# LVDS_IFC_HVAMP.net
KiCad netlist of a schematic drawn in Altium Designer
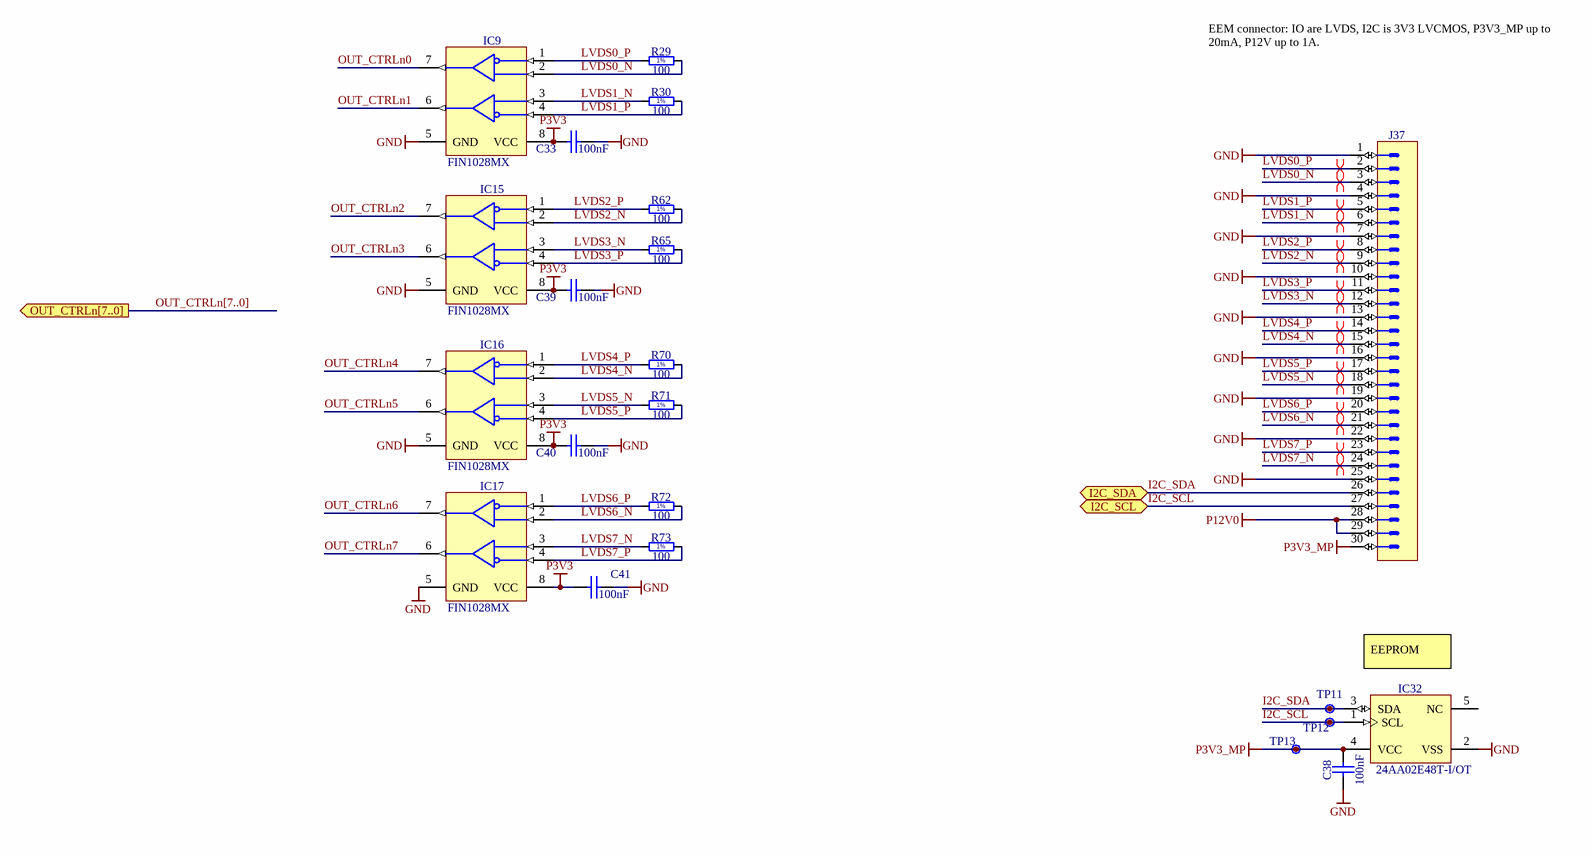
[diagram p0: LVDS_IFC_HVAMP.SchDoc]

(export (version "E")
  (design (tool "Eeschema 10.0.6"))
  (components
    (comp (ref "C33")
      (value "100nF")
      (footprint "CAPC1005X55N")
      (description "Non-polarised capacitor")
      (fields
        (field (name "PART NUMBER") "CC0402_100NF_16V_10%_X5R")
        (field (name "VOLTAGE") "16V")
        (field (name "AUTHOR") "CERN DEM JLC")
      )
      (libsource (lib "Capacitors") (part "Capacitor - non polarized"))
    )
    (comp (ref "C38")
      (value "100nF")
      (footprint "CAPC1005X55N")
      (description "Non-polarised capacitor")
      (fields
        (field (name "PART NUMBER") "CC0402_100NF_16V_10%_X5R")
        (field (name "VOLTAGE") "16V")
        (field (name "AUTHOR") "CERN DEM JLC")
      )
      (libsource (lib "Capacitors") (part "Capacitor - non polarized"))
    )
    (comp (ref "C39")
      (value "100nF")
      (footprint "CAPC1005X55N")
      (description "Non-polarised capacitor")
      (fields
        (field (name "PART NUMBER") "CC0402_100NF_16V_10%_X5R")
        (field (name "VOLTAGE") "16V")
        (field (name "AUTHOR") "CERN DEM JLC")
      )
      (libsource (lib "Capacitors") (part "Capacitor - non polarized"))
    )
    (comp (ref "C40")
      (value "100nF")
      (footprint "CAPC1005X55N")
      (description "Non-polarised capacitor")
      (fields
        (field (name "PART NUMBER") "CC0402_100NF_16V_10%_X5R")
        (field (name "VOLTAGE") "16V")
        (field (name "AUTHOR") "CERN DEM JLC")
      )
      (libsource (lib "Capacitors") (part "Capacitor - non polarized"))
    )
    (comp (ref "C41")
      (value "100nF")
      (footprint "CAPC1005X55N")
      (description "Non-polarised capacitor")
      (fields
        (field (name "PART NUMBER") "CC0402_100NF_16V_10%_X5R")
        (field (name "VOLTAGE") "16V")
        (field (name "AUTHOR") "CERN DEM JLC")
      )
      (libsource (lib "Capacitors") (part "Capacitor - non polarized"))
    )
    (comp (ref "IC9")
      (value "FIN1028MX")
      (footprint "SOIC127P600X175-8N")
      (description "3.3V LVDS 2-Bit High-Speed Differential Reciever")
      (fields (field (name "MANUFACTURER") "ON Semiconductor") (field (name "AUTHOR") "GK"))
      (libsource (lib "LIBRARY_SCH") (part "IFC_FIN1028"))
    )
    (comp (ref "IC15")
      (value "FIN1028MX")
      (footprint "SOIC127P600X175-8N")
      (description "3.3V LVDS 2-Bit High-Speed Differential Reciever")
      (fields (field (name "MANUFACTURER") "ON Semiconductor") (field (name "AUTHOR") "GK"))
      (libsource (lib "LIBRARY_SCH") (part "IFC_FIN1028"))
    )
    (comp (ref "IC16")
      (value "FIN1028MX")
      (footprint "SOIC127P600X175-8N")
      (description "3.3V LVDS 2-Bit High-Speed Differential Reciever")
      (fields (field (name "MANUFACTURER") "ON Semiconductor") (field (name "AUTHOR") "GK"))
      (libsource (lib "LIBRARY_SCH") (part "IFC_FIN1028"))
    )
    (comp (ref "IC17")
      (value "FIN1028MX")
      (footprint "SOIC127P600X175-8N")
      (description "3.3V LVDS 2-Bit High-Speed Differential Reciever")
      (fields (field (name "MANUFACTURER") "ON Semiconductor") (field (name "AUTHOR") "GK"))
      (libsource (lib "LIBRARY_SCH") (part "IFC_FIN1028"))
    )
    (comp (ref "IC32")
      (value "24AA02E48T-I/OT")
      (footprint "SOT95P280X145-5N")
      (description "1.7V-5.5V, 2K I2C Serial EEPROM With EUI-48 Node Identity")
      (fields (field (name "MANUFACTURER") "MICROCHIP TECHNOLOGY") (field (name "AUTHOR") "CERN DEM MR"))
      (libsource (lib "ICs And Semiconductors") (part "24AA02E48T-I/OT"))
    )
    (comp (ref "J37")
      (value "~")
      (footprint "3M_N2530-6002RB")
      (description "Connector 30 Male")
      (fields
        (field (name "PART NUMBER") "3M_N2530-6002RB")
        (field (name "MANUFACTURER") "3M")
        (field (name "AUTHOR") "CERN DEM JLC")
      )
      (libsource (lib "Connectors") (part "Connector 30 Male"))
    )
    (comp (ref "R29")
      (value "100")
      (footprint "RESC1005X40N")
      (description "Resistor - 1%")
      (fields
        (field (name "PART NUMBER") "R0402_100R_1%_0.0625W_100PPM")
        (field (name "POWER") "0.0625W")
        (field (name "AUTHOR") "CERN DEM JLC")
      )
      (libsource (lib "Resistors") (part "Resistor - 1%"))
    )
    (comp (ref "R30")
      (value "100")
      (footprint "RESC1005X40N")
      (description "Resistor - 1%")
      (fields
        (field (name "PART NUMBER") "R0402_100R_1%_0.0625W_100PPM")
        (field (name "POWER") "0.0625W")
        (field (name "AUTHOR") "CERN DEM JLC")
      )
      (libsource (lib "Resistors") (part "Resistor - 1%"))
    )
    (comp (ref "R62")
      (value "100")
      (footprint "RESC1005X40N")
      (description "Resistor - 1%")
      (fields
        (field (name "PART NUMBER") "R0402_100R_1%_0.0625W_100PPM")
        (field (name "POWER") "0.0625W")
        (field (name "AUTHOR") "CERN DEM JLC")
      )
      (libsource (lib "Resistors") (part "Resistor - 1%"))
    )
    (comp (ref "R65")
      (value "100")
      (footprint "RESC1005X40N")
      (description "Resistor - 1%")
      (fields
        (field (name "PART NUMBER") "R0402_100R_1%_0.0625W_100PPM")
        (field (name "POWER") "0.0625W")
        (field (name "AUTHOR") "CERN DEM JLC")
      )
      (libsource (lib "Resistors") (part "Resistor - 1%"))
    )
    (comp (ref "R70")
      (value "100")
      (footprint "RESC1005X40N")
      (description "Resistor - 1%")
      (fields
        (field (name "PART NUMBER") "R0402_100R_1%_0.0625W_100PPM")
        (field (name "POWER") "0.0625W")
        (field (name "AUTHOR") "CERN DEM JLC")
      )
      (libsource (lib "Resistors") (part "Resistor - 1%"))
    )
    (comp (ref "R71")
      (value "100")
      (footprint "RESC1005X40N")
      (description "Resistor - 1%")
      (fields
        (field (name "PART NUMBER") "R0402_100R_1%_0.0625W_100PPM")
        (field (name "POWER") "0.0625W")
        (field (name "AUTHOR") "CERN DEM JLC")
      )
      (libsource (lib "Resistors") (part "Resistor - 1%"))
    )
    (comp (ref "R72")
      (value "100")
      (footprint "RESC1005X40N")
      (description "Resistor - 1%")
      (fields
        (field (name "PART NUMBER") "R0402_100R_1%_0.0625W_100PPM")
        (field (name "POWER") "0.0625W")
        (field (name "AUTHOR") "CERN DEM JLC")
      )
      (libsource (lib "Resistors") (part "Resistor - 1%"))
    )
    (comp (ref "R73")
      (value "100")
      (footprint "RESC1005X40N")
      (description "Resistor - 1%")
      (fields
        (field (name "PART NUMBER") "R0402_100R_1%_0.0625W_100PPM")
        (field (name "POWER") "0.0625W")
        (field (name "AUTHOR") "CERN DEM JLC")
      )
      (libsource (lib "Resistors") (part "Resistor - 1%"))
    )
    (comp (ref "TP11")
      (value "Test Point")
      (footprint "TPS127")
      (fields (field (name "PART NUMBER") "SMD_PAD_1.27X1.27MM") (field (name "AUTHOR") "CERN DEM JLC"))
      (libsource (lib "Eletro-mechanical") (part "Test Point"))
    )
    (comp (ref "TP12")
      (value "Test Point")
      (footprint "TPS127")
      (fields (field (name "PART NUMBER") "SMD_PAD_1.27X1.27MM") (field (name "AUTHOR") "CERN DEM JLC"))
      (libsource (lib "Eletro-mechanical") (part "Test Point"))
    )
    (comp (ref "TP13")
      (value "Test Point")
      (footprint "TPS127")
      (fields (field (name "PART NUMBER") "SMD_PAD_1.27X1.27MM") (field (name "AUTHOR") "CERN DEM JLC"))
      (libsource (lib "Eletro-mechanical") (part "Test Point"))
    )
  )
  (nets
    (net (code "1") (name "/I2C_SCL") (class "Default")
      (node (ref "IC32") (pin "1") (pinfunction "SCL_1") (pintype "input"))
      (node (ref "J37") (pin "27") (pinfunction "27_27") (pintype "bidirectional"))
      (node (ref "TP12") (pin "1") (pinfunction "1_1") (pintype "bidirectional"))
    )
    (net (code "2") (name "/I2C_SDA") (class "Default")
      (node (ref "IC32") (pin "3") (pinfunction "SDA_3") (pintype "bidirectional"))
      (node (ref "J37") (pin "26") (pinfunction "26_26") (pintype "bidirectional"))
      (node (ref "TP11") (pin "1") (pinfunction "1_1") (pintype "bidirectional"))
    )
    (net (code "3") (name "/LVDS0_N") (class "Default")
      (node (ref "IC9") (pin "2") (pinfunction "RIN1+_2") (pintype "input"))
      (node (ref "J37") (pin "3") (pinfunction "3_3") (pintype "bidirectional"))
      (node (ref "R29") (pin "2") (pinfunction "2_2") (pintype "passive"))
    )
    (net (code "4") (name "/LVDS0_P") (class "Default")
      (node (ref "IC9") (pin "1") (pinfunction "RIN1-_1") (pintype "input"))
      (node (ref "J37") (pin "2") (pinfunction "2_2") (pintype "bidirectional"))
      (node (ref "R29") (pin "1") (pinfunction "1_1") (pintype "passive"))
    )
    (net (code "5") (name "/LVDS1_N") (class "Default")
      (node (ref "IC9") (pin "3") (pinfunction "RIN2+_3") (pintype "input"))
      (node (ref "J37") (pin "6") (pinfunction "6_6") (pintype "bidirectional"))
      (node (ref "R30") (pin "1") (pinfunction "1_1") (pintype "passive"))
    )
    (net (code "6") (name "/LVDS1_P") (class "Default")
      (node (ref "IC9") (pin "4") (pinfunction "RIN2-_4") (pintype "input"))
      (node (ref "J37") (pin "5") (pinfunction "5_5") (pintype "bidirectional"))
      (node (ref "R30") (pin "2") (pinfunction "2_2") (pintype "passive"))
    )
    (net (code "7") (name "/LVDS2_N") (class "Default")
      (node (ref "IC15") (pin "2") (pinfunction "RIN1+_2") (pintype "input"))
      (node (ref "J37") (pin "9") (pinfunction "9_9") (pintype "bidirectional"))
      (node (ref "R62") (pin "2") (pinfunction "2_2") (pintype "passive"))
    )
    (net (code "8") (name "/LVDS2_P") (class "Default")
      (node (ref "IC15") (pin "1") (pinfunction "RIN1-_1") (pintype "input"))
      (node (ref "J37") (pin "8") (pinfunction "8_8") (pintype "bidirectional"))
      (node (ref "R62") (pin "1") (pinfunction "1_1") (pintype "passive"))
    )
    (net (code "9") (name "/LVDS3_N") (class "Default")
      (node (ref "IC15") (pin "3") (pinfunction "RIN2+_3") (pintype "input"))
      (node (ref "J37") (pin "12") (pinfunction "12_12") (pintype "bidirectional"))
      (node (ref "R65") (pin "1") (pinfunction "1_1") (pintype "passive"))
    )
    (net (code "10") (name "/LVDS3_P") (class "Default")
      (node (ref "IC15") (pin "4") (pinfunction "RIN2-_4") (pintype "input"))
      (node (ref "J37") (pin "11") (pinfunction "11_11") (pintype "bidirectional"))
      (node (ref "R65") (pin "2") (pinfunction "2_2") (pintype "passive"))
    )
    (net (code "11") (name "/LVDS4_N") (class "Default")
      (node (ref "IC16") (pin "2") (pinfunction "RIN1+_2") (pintype "input"))
      (node (ref "J37") (pin "15") (pinfunction "15_15") (pintype "bidirectional"))
      (node (ref "R70") (pin "2") (pinfunction "2_2") (pintype "passive"))
    )
    (net (code "12") (name "/LVDS4_P") (class "Default")
      (node (ref "IC16") (pin "1") (pinfunction "RIN1-_1") (pintype "input"))
      (node (ref "J37") (pin "14") (pinfunction "14_14") (pintype "bidirectional"))
      (node (ref "R70") (pin "1") (pinfunction "1_1") (pintype "passive"))
    )
    (net (code "13") (name "/LVDS5_N") (class "Default")
      (node (ref "IC16") (pin "3") (pinfunction "RIN2+_3") (pintype "input"))
      (node (ref "J37") (pin "18") (pinfunction "18_18") (pintype "bidirectional"))
      (node (ref "R71") (pin "1") (pinfunction "1_1") (pintype "passive"))
    )
    (net (code "14") (name "/LVDS5_P") (class "Default")
      (node (ref "IC16") (pin "4") (pinfunction "RIN2-_4") (pintype "input"))
      (node (ref "J37") (pin "17") (pinfunction "17_17") (pintype "bidirectional"))
      (node (ref "R71") (pin "2") (pinfunction "2_2") (pintype "passive"))
    )
    (net (code "15") (name "/LVDS6_N") (class "Default")
      (node (ref "IC17") (pin "2") (pinfunction "RIN1+_2") (pintype "input"))
      (node (ref "J37") (pin "21") (pinfunction "21_21") (pintype "bidirectional"))
      (node (ref "R72") (pin "2") (pinfunction "2_2") (pintype "passive"))
    )
    (net (code "16") (name "/LVDS6_P") (class "Default")
      (node (ref "IC17") (pin "1") (pinfunction "RIN1-_1") (pintype "input"))
      (node (ref "J37") (pin "20") (pinfunction "20_20") (pintype "bidirectional"))
      (node (ref "R72") (pin "1") (pinfunction "1_1") (pintype "passive"))
    )
    (net (code "17") (name "/LVDS7_N") (class "Default")
      (node (ref "IC17") (pin "3") (pinfunction "RIN2+_3") (pintype "input"))
      (node (ref "J37") (pin "24") (pinfunction "24_24") (pintype "bidirectional"))
      (node (ref "R73") (pin "1") (pinfunction "1_1") (pintype "passive"))
    )
    (net (code "18") (name "/LVDS7_P") (class "Default")
      (node (ref "IC17") (pin "4") (pinfunction "RIN2-_4") (pintype "input"))
      (node (ref "J37") (pin "23") (pinfunction "23_23") (pintype "bidirectional"))
      (node (ref "R73") (pin "2") (pinfunction "2_2") (pintype "passive"))
    )
    (net (code "19") (name "/OUT_CTRLn0") (class "Default")
      (node (ref "IC9") (pin "7") (pinfunction "ROUT1_7") (pintype "output"))
    )
    (net (code "20") (name "/OUT_CTRLn1") (class "Default")
      (node (ref "IC9") (pin "6") (pinfunction "ROUT2_6") (pintype "output"))
    )
    (net (code "21") (name "/OUT_CTRLn2") (class "Default")
      (node (ref "IC15") (pin "7") (pinfunction "ROUT1_7") (pintype "output"))
    )
    (net (code "22") (name "/OUT_CTRLn3") (class "Default")
      (node (ref "IC15") (pin "6") (pinfunction "ROUT2_6") (pintype "output"))
    )
    (net (code "23") (name "/OUT_CTRLn4") (class "Default")
      (node (ref "IC16") (pin "7") (pinfunction "ROUT1_7") (pintype "output"))
    )
    (net (code "24") (name "/OUT_CTRLn5") (class "Default")
      (node (ref "IC16") (pin "6") (pinfunction "ROUT2_6") (pintype "output"))
    )
    (net (code "25") (name "/OUT_CTRLn6") (class "Default")
      (node (ref "IC17") (pin "7") (pinfunction "ROUT1_7") (pintype "output"))
    )
    (net (code "26") (name "/OUT_CTRLn7") (class "Default")
      (node (ref "IC17") (pin "6") (pinfunction "ROUT2_6") (pintype "output"))
    )
    (net (code "28") (name "GND") (class "Default")
      (node (ref "C33") (pin "1") (pinfunction "1_1") (pintype "passive"))
      (node (ref "C38") (pin "1") (pinfunction "1_1") (pintype "passive"))
      (node (ref "C39") (pin "1") (pinfunction "1_1") (pintype "passive"))
      (node (ref "C40") (pin "1") (pinfunction "1_1") (pintype "passive"))
      (node (ref "C41") (pin "1") (pinfunction "1_1") (pintype "passive"))
      (node (ref "IC15") (pin "5") (pinfunction "GND_5") (pintype "power_in"))
      (node (ref "IC16") (pin "5") (pinfunction "GND_5") (pintype "power_in"))
      (node (ref "IC17") (pin "5") (pinfunction "GND_5") (pintype "power_in"))
      (node (ref "IC32") (pin "2") (pinfunction "VSS_2") (pintype "power_in"))
      (node (ref "IC9") (pin "5") (pinfunction "GND_5") (pintype "power_in"))
      (node (ref "J37") (pin "1") (pinfunction "1_1") (pintype "bidirectional"))
      (node (ref "J37") (pin "10") (pinfunction "10_10") (pintype "bidirectional"))
      (node (ref "J37") (pin "13") (pinfunction "13_13") (pintype "bidirectional"))
      (node (ref "J37") (pin "16") (pinfunction "16_16") (pintype "bidirectional"))
      (node (ref "J37") (pin "19") (pinfunction "19_19") (pintype "bidirectional"))
      (node (ref "J37") (pin "22") (pinfunction "22_22") (pintype "bidirectional"))
      (node (ref "J37") (pin "25") (pinfunction "25_25") (pintype "bidirectional"))
      (node (ref "J37") (pin "4") (pinfunction "4_4") (pintype "bidirectional"))
      (node (ref "J37") (pin "7") (pinfunction "7_7") (pintype "bidirectional"))
    )
    (net (code "29") (name "P3V3") (class "Default")
      (node (ref "C33") (pin "2") (pinfunction "2_2") (pintype "passive"))
      (node (ref "C39") (pin "2") (pinfunction "2_2") (pintype "passive"))
      (node (ref "C40") (pin "2") (pinfunction "2_2") (pintype "passive"))
      (node (ref "C41") (pin "2") (pinfunction "2_2") (pintype "passive"))
      (node (ref "IC15") (pin "8") (pinfunction "VCC_8") (pintype "power_in"))
      (node (ref "IC16") (pin "8") (pinfunction "VCC_8") (pintype "power_in"))
      (node (ref "IC17") (pin "8") (pinfunction "VCC_8") (pintype "power_in"))
      (node (ref "IC9") (pin "8") (pinfunction "VCC_8") (pintype "power_in"))
    )
    (net (code "30") (name "P3V3_MP") (class "Default")
      (node (ref "C38") (pin "2") (pinfunction "2_2") (pintype "passive"))
      (node (ref "IC32") (pin "4") (pinfunction "VCC_4") (pintype "power_in"))
      (node (ref "J37") (pin "30") (pinfunction "30_30") (pintype "bidirectional"))
      (node (ref "TP13") (pin "1") (pinfunction "1_1") (pintype "bidirectional"))
    )
    (net (code "31") (name "P12V0") (class "Default")
      (node (ref "J37") (pin "28") (pinfunction "28_28") (pintype "bidirectional"))
      (node (ref "J37") (pin "29") (pinfunction "29_29") (pintype "bidirectional"))
    )
    (net (code "32") (name "unconnected-(IC32-NC-Pad5)") (class "Default")
      (node (ref "IC32") (pin "5") (pinfunction "NC_5") (pintype "passive"))
    )
  )
)
